# emonBike_v0_1.net
KiCad netlist of a schematic drawn in EAGLE
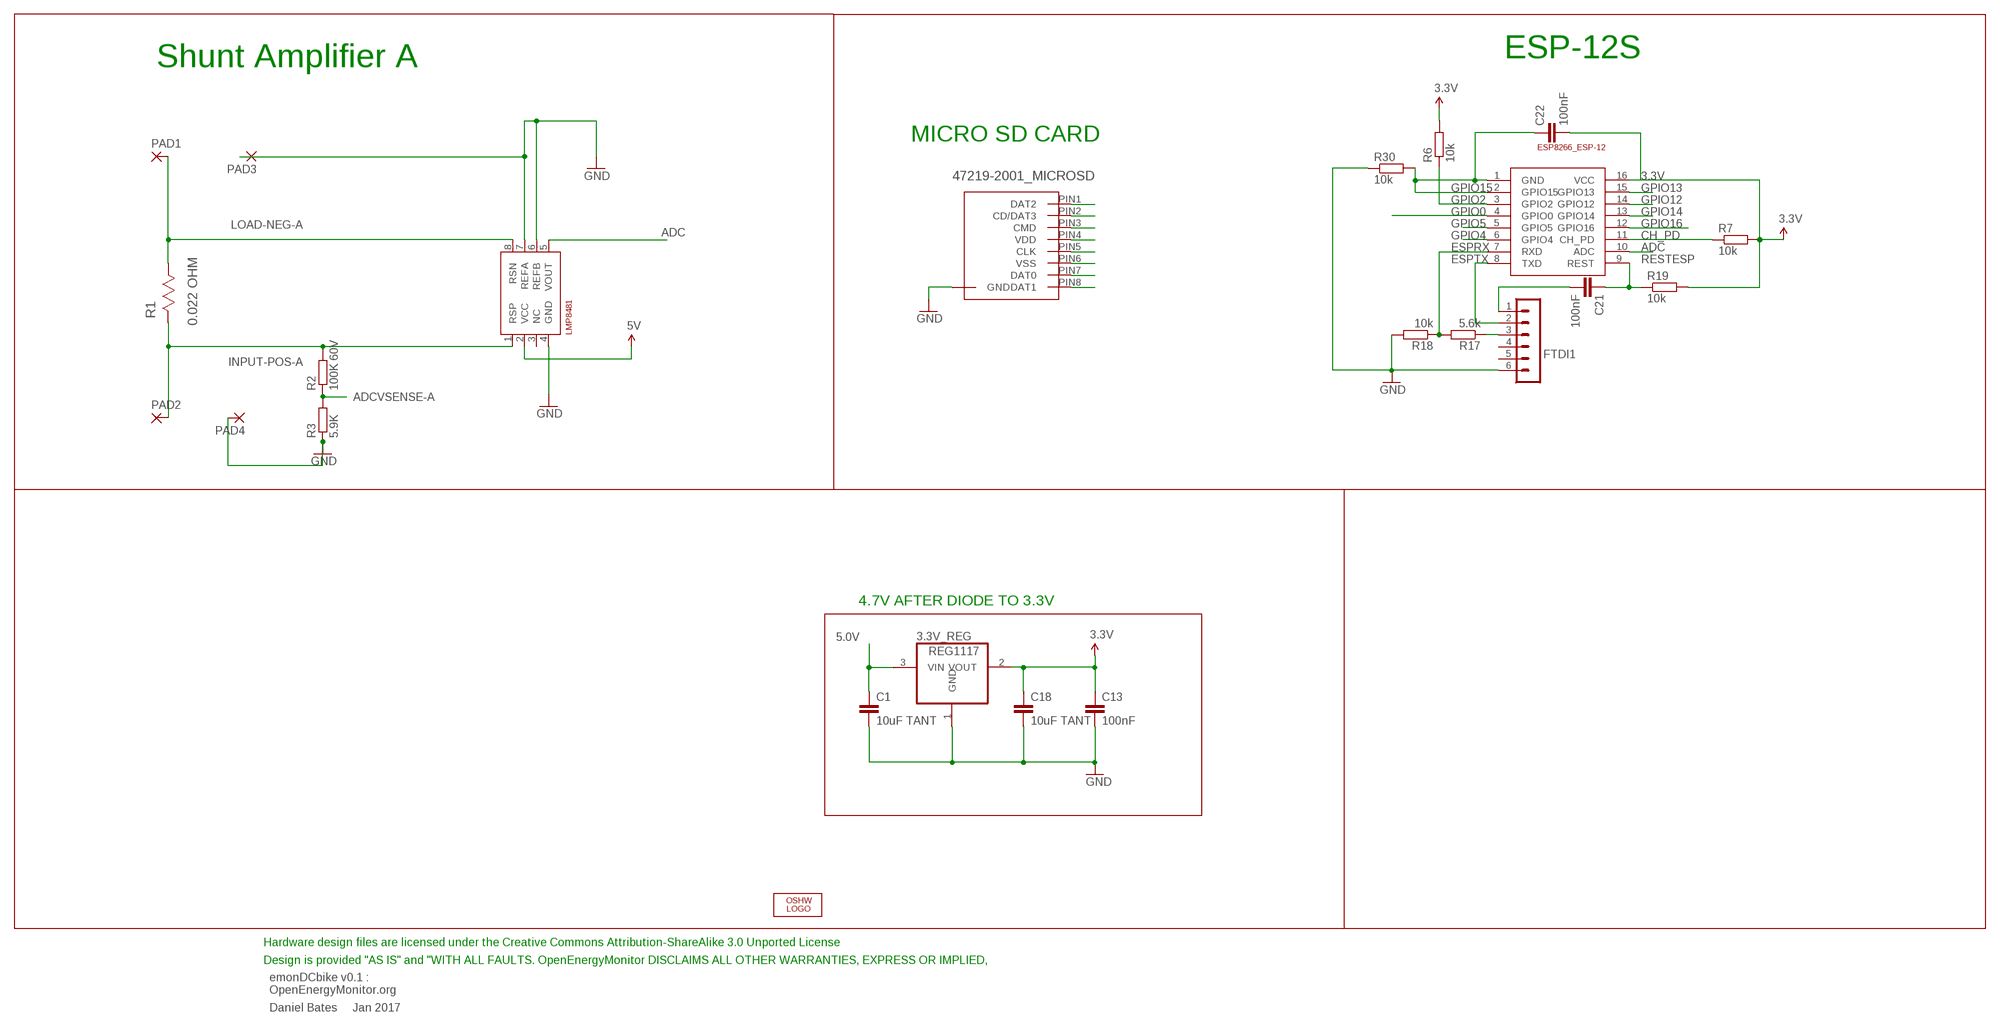
[diagram p0: schematic, sheet 1]

(export (version "E")
  (design (tool "Eeschema 10.0.6"))
  (components
    (comp (ref "3.3V_REG")
      (value "REG1117")
      (footprint "eagle-import:SOT223")
      (fields (field (name "MF") "TEXAS INSTRUMENTS"))
      (libsource (lib "eagle-import") (part "REG1117"))
    )
    (comp (ref "C1")
      (value "10uF TANT")
      (footprint "eagle-import:C0603")
      (libsource (lib "eagle-import") (part "C-EUC0603"))
    )
    (comp (ref "C13")
      (value "100nF")
      (footprint "eagle-import:C0603")
      (libsource (lib "eagle-import") (part "C-EUC0603"))
    )
    (comp (ref "C18")
      (value "10uF TANT")
      (footprint "eagle-import:C0603")
      (libsource (lib "eagle-import") (part "C-EUC0603"))
    )
    (comp (ref "C21")
      (value "100nF")
      (footprint "eagle-import:C0603")
      (libsource (lib "eagle-import") (part "C-EUC0603"))
    )
    (comp (ref "C22")
      (value "100nF")
      (footprint "eagle-import:C0603")
      (libsource (lib "eagle-import") (part "C-EUC0603"))
    )
    (comp (ref "ESP-12")
      (value "ESP8266_ESP-12")
      (footprint "eagle-import:ESP8266-ESP12")
      (libsource (lib "eagle-import") (part "ESP8266_ESP-12"))
    )
    (comp (ref "FTDI1")
      (value "FTDI-ESP")
      (footprint "eagle-import:MA06-1")
      (libsource (lib "eagle-import") (part "MA06-1"))
    )
    (comp (ref "LOGO1")
      (value "OSHW_LOGO_6MILX0200-NT")
      (footprint "eagle-import:OSHW_6X200_NOTEXT")
      (libsource (lib "eagle-import") (part "OSHW_LOGO_6MILX0200-NT"))
    )
    (comp (ref "PAD1")
      (value "3,81/1,4")
      (footprint "eagle-import:3,81_1,4")
      (libsource (lib "eagle-import") (part "3,81/1,4"))
    )
    (comp (ref "PAD2")
      (value "3,81/1,4")
      (footprint "eagle-import:3,81_1,4")
      (libsource (lib "eagle-import") (part "3,81/1,4"))
    )
    (comp (ref "PAD3")
      (value "3,81/1,4")
      (footprint "eagle-import:3,81_1,4")
      (libsource (lib "eagle-import") (part "3,81/1,4"))
    )
    (comp (ref "PAD4")
      (value "3,81/1,4")
      (footprint "eagle-import:3,81_1,4")
      (libsource (lib "eagle-import") (part "3,81/1,4"))
    )
    (comp (ref "R1")
      (value "0.022 OHM")
      (footprint "eagle-import:RESC3216X71N")
      (fields (field (name "MPN") "ERJ-8CWFR022V") (field (name "TOLERANCE") "± 1 %"))
      (libsource (lib "eagle-import") (part "ERJ-8CWFR022V"))
    )
    (comp (ref "R2")
      (value "100K 60V")
      (footprint "eagle-import:R0603")
      (fields (field (name "MPN") "MCWR06X1003FTL"))
      (libsource (lib "eagle-import") (part "R-EU_R0603"))
    )
    (comp (ref "R3")
      (value "5.9K")
      (footprint "eagle-import:R0603")
      (fields (field (name "MPN") " MCWR06X5901FTL"))
      (libsource (lib "eagle-import") (part "R-EU_R0603"))
    )
    (comp (ref "R6")
      (value "10k")
      (footprint "eagle-import:R0603")
      (libsource (lib "eagle-import") (part "R-EU_R0603"))
    )
    (comp (ref "R7")
      (value "10k")
      (footprint "eagle-import:R0603")
      (libsource (lib "eagle-import") (part "R-EU_R0603"))
    )
    (comp (ref "R17")
      (value "5.6k")
      (footprint "eagle-import:R0603")
      (libsource (lib "eagle-import") (part "R-EU_R0603"))
    )
    (comp (ref "R18")
      (value "10k")
      (footprint "eagle-import:R0603")
      (libsource (lib "eagle-import") (part "R-EU_R0603"))
    )
    (comp (ref "R19")
      (value "10k")
      (footprint "eagle-import:R0603")
      (libsource (lib "eagle-import") (part "R-EU_R0603"))
    )
    (comp (ref "R30")
      (value "10k")
      (footprint "eagle-import:R0603")
      (libsource (lib "eagle-import") (part "R-EU_R0603"))
    )
    (comp (ref "SHUNTMON-A")
      (value "LMP8481")
      (footprint "eagle-import:S-PDSO-G08")
      (fields (field (name "MF") "TEXAS INSTRUMENTS") (field (name "MPN") "LMP8481MME-S/NOPB"))
      (libsource (lib "eagle-import") (part "LMP8481LMP8481-H"))
    )
    (comp (ref "U$1")
      (value "47219-2001_MICROSD")
      (footprint "eagle-import:47219-2001_MICROSD")
      (libsource (lib "eagle-import") (part "47219-2001_MICROSD"))
    )
  )
  (nets
    (net (code "1") (name "/5.0V") (class "Default")
      (node (ref "3.3V_REG") (pin "3") (pinfunction "VIN_3") (pintype "input"))
      (node (ref "C1") (pin "1") (pinfunction "1_1") (pintype "passive"))
    )
    (net (code "2") (name "/ADC") (class "Default")
      (node (ref "ESP-12") (pin "10") (pinfunction "ADC_10") (pintype "bidirectional"))
      (node (ref "SHUNTMON-A") (pin "5") (pinfunction "VOUT_5") (pintype "bidirectional"))
    )
    (net (code "3") (name "/ADCVSENSE-A") (class "Default")
      (node (ref "R2") (pin "1") (pinfunction "1_1") (pintype "passive"))
      (node (ref "R3") (pin "2") (pinfunction "2_2") (pintype "passive"))
    )
    (net (code "4") (name "/CH_PD") (class "Default")
      (node (ref "ESP-12") (pin "11") (pinfunction "CH_PD_11") (pintype "bidirectional"))
      (node (ref "R7") (pin "1") (pinfunction "1_1") (pintype "passive"))
    )
    (net (code "5") (name "/ESPRX") (class "Default")
      (node (ref "ESP-12") (pin "7") (pinfunction "RXD_7") (pintype "bidirectional"))
      (node (ref "R17") (pin "2") (pinfunction "2_2") (pintype "passive"))
      (node (ref "R18") (pin "1") (pinfunction "1_1") (pintype "passive"))
    )
    (net (code "6") (name "/ESPTX") (class "Default")
      (node (ref "ESP-12") (pin "8") (pinfunction "TXD_8") (pintype "bidirectional"))
      (node (ref "FTDI1") (pin "2") (pinfunction "2_2") (pintype "passive"))
    )
    (net (code "7") (name "/GPIO0") (class "Default")
      (node (ref "ESP-12") (pin "4") (pinfunction "GPIO0_4") (pintype "bidirectional"))
    )
    (net (code "8") (name "/GPIO2") (class "Default")
      (node (ref "ESP-12") (pin "3") (pinfunction "GPIO2_3") (pintype "bidirectional"))
      (node (ref "R6") (pin "1") (pinfunction "1_1") (pintype "passive"))
      (node (ref "U$1") (pin "PIN2") (pinfunction "CD/DAT3_PIN2") (pintype "bidirectional"))
    )
    (net (code "9") (name "/GPIO4") (class "Default")
      (node (ref "ESP-12") (pin "6") (pinfunction "GPIO4_6") (pintype "bidirectional"))
    )
    (net (code "10") (name "/GPIO5") (class "Default")
      (node (ref "ESP-12") (pin "5") (pinfunction "GPIO5_5") (pintype "bidirectional"))
    )
    (net (code "11") (name "/GPIO12") (class "Default")
      (node (ref "ESP-12") (pin "14") (pinfunction "GPIO12_14") (pintype "bidirectional"))
      (node (ref "U$1") (pin "PIN7") (pinfunction "DAT0_PIN7") (pintype "bidirectional"))
    )
    (net (code "12") (name "/GPIO13") (class "Default")
      (node (ref "ESP-12") (pin "15") (pinfunction "GPIO13_15") (pintype "bidirectional"))
      (node (ref "U$1") (pin "PIN3") (pinfunction "CMD_PIN3") (pintype "bidirectional"))
    )
    (net (code "13") (name "/GPIO14") (class "Default")
      (node (ref "ESP-12") (pin "13") (pinfunction "GPIO14_13") (pintype "bidirectional"))
      (node (ref "U$1") (pin "PIN5") (pinfunction "CLK_PIN5") (pintype "bidirectional"))
    )
    (net (code "14") (name "/GPIO15") (class "Default")
      (node (ref "C22") (pin "1") (pinfunction "1_1") (pintype "passive"))
      (node (ref "ESP-12") (pin "1") (pinfunction "GND_1") (pintype "bidirectional"))
      (node (ref "ESP-12") (pin "2") (pinfunction "GPIO15_2") (pintype "bidirectional"))
      (node (ref "R30") (pin "2") (pinfunction "2_2") (pintype "passive"))
    )
    (net (code "15") (name "/GPIO16") (class "Default")
      (node (ref "ESP-12") (pin "12") (pinfunction "GPIO16_12") (pintype "bidirectional"))
    )
    (net (code "16") (name "/INPUT-POS-A") (class "Default")
      (node (ref "PAD2") (pin "1") (pinfunction "P_1") (pintype "passive"))
      (node (ref "R1") (pin "2") (pinfunction "R2_2") (pintype "passive"))
      (node (ref "R2") (pin "2") (pinfunction "2_2") (pintype "passive"))
      (node (ref "SHUNTMON-A") (pin "1") (pinfunction "RSP_1") (pintype "bidirectional"))
    )
    (net (code "17") (name "/LOAD-NEG-A") (class "Default")
      (node (ref "PAD1") (pin "1") (pinfunction "P_1") (pintype "passive"))
      (node (ref "R1") (pin "1") (pinfunction "R1_1") (pintype "passive"))
      (node (ref "SHUNTMON-A") (pin "8") (pinfunction "RSN_8") (pintype "bidirectional"))
    )
    (net (code "18") (name "/RESTESP") (class "Default")
      (node (ref "C21") (pin "1") (pinfunction "1_1") (pintype "passive"))
      (node (ref "ESP-12") (pin "9") (pinfunction "REST_9") (pintype "bidirectional"))
      (node (ref "R19") (pin "1") (pinfunction "1_1") (pintype "passive"))
    )
    (net (code "19") (name "3.3V") (class "Default")
      (node (ref "3.3V_REG") (pin "2") (pinfunction "VOUT_2") (pintype "output"))
      (node (ref "C13") (pin "1") (pinfunction "1_1") (pintype "passive"))
      (node (ref "C18") (pin "1") (pinfunction "1_1") (pintype "passive"))
      (node (ref "C22") (pin "2") (pinfunction "2_2") (pintype "passive"))
      (node (ref "ESP-12") (pin "16") (pinfunction "VCC_16") (pintype "bidirectional"))
      (node (ref "R19") (pin "2") (pinfunction "2_2") (pintype "passive"))
      (node (ref "R6") (pin "2") (pinfunction "2_2") (pintype "passive"))
      (node (ref "R7") (pin "2") (pinfunction "2_2") (pintype "passive"))
      (node (ref "U$1") (pin "PIN4") (pinfunction "VDD_PIN4") (pintype "bidirectional"))
    )
    (net (code "20") (name "5V") (class "Default")
      (node (ref "SHUNTMON-A") (pin "2") (pinfunction "VCC_2") (pintype "bidirectional"))
    )
    (net (code "21") (name "GND") (class "Default")
      (node (ref "3.3V_REG") (pin "1") (pinfunction "GND_1") (pintype "power_in"))
      (node (ref "C1") (pin "2") (pinfunction "2_2") (pintype "passive"))
      (node (ref "C13") (pin "2") (pinfunction "2_2") (pintype "passive"))
      (node (ref "C18") (pin "2") (pinfunction "2_2") (pintype "passive"))
      (node (ref "FTDI1") (pin "6") (pinfunction "6_6") (pintype "passive"))
      (node (ref "PAD3") (pin "1") (pinfunction "P_1") (pintype "passive"))
      (node (ref "PAD4") (pin "1") (pinfunction "P_1") (pintype "passive"))
      (node (ref "R18") (pin "2") (pinfunction "2_2") (pintype "passive"))
      (node (ref "R3") (pin "1") (pinfunction "1_1") (pintype "passive"))
      (node (ref "R30") (pin "1") (pinfunction "1_1") (pintype "passive"))
      (node (ref "SHUNTMON-A") (pin "4") (pinfunction "GND_4") (pintype "bidirectional"))
      (node (ref "SHUNTMON-A") (pin "6") (pinfunction "REFB_6") (pintype "bidirectional"))
      (node (ref "SHUNTMON-A") (pin "7") (pinfunction "REFA_7") (pintype "bidirectional"))
      (node (ref "U$1") (pin "P$1") (pinfunction "GND_P$1") (pintype "bidirectional"))
      (node (ref "U$1") (pin "P$2") (pinfunction "GND_P$2") (pintype "bidirectional"))
      (node (ref "U$1") (pin "P$3") (pinfunction "GND_P$3") (pintype "bidirectional"))
      (node (ref "U$1") (pin "P$4") (pinfunction "GND_P$4") (pintype "bidirectional"))
      (node (ref "U$1") (pin "PIN6") (pinfunction "VSS_PIN6") (pintype "bidirectional"))
    )
    (net (code "22") (name "Net-(C21-Pad2)") (class "Default")
      (node (ref "C21") (pin "2") (pinfunction "2_2") (pintype "passive"))
      (node (ref "FTDI1") (pin "1") (pinfunction "1_1") (pintype "passive"))
    )
    (net (code "23") (name "Net-(FTDI1-Pad3)") (class "Default")
      (node (ref "FTDI1") (pin "3") (pinfunction "3_3") (pintype "passive"))
      (node (ref "R17") (pin "1") (pinfunction "1_1") (pintype "passive"))
    )
    (net (code "24") (name "unconnected-(FTDI1-Pad4)") (class "Default")
      (node (ref "FTDI1") (pin "4") (pinfunction "4_4") (pintype "passive"))
    )
    (net (code "25") (name "unconnected-(FTDI1-Pad5)") (class "Default")
      (node (ref "FTDI1") (pin "5") (pinfunction "5_5") (pintype "passive"))
    )
    (net (code "26") (name "unconnected-(SHUNTMON-A-NC-Pad3)") (class "Default")
      (node (ref "SHUNTMON-A") (pin "3") (pinfunction "NC_3") (pintype "bidirectional"))
    )
    (net (code "27") (name "unconnected-(U$1-DAT1-PadPIN8)") (class "Default")
      (node (ref "U$1") (pin "PIN8") (pinfunction "DAT1_PIN8") (pintype "bidirectional"))
    )
    (net (code "28") (name "unconnected-(U$1-DAT2-PadPIN1)") (class "Default")
      (node (ref "U$1") (pin "PIN1") (pinfunction "DAT2_PIN1") (pintype "bidirectional"))
    )
  )
)
